# MotorShield.net
KiCad netlist of a schematic drawn in EAGLE
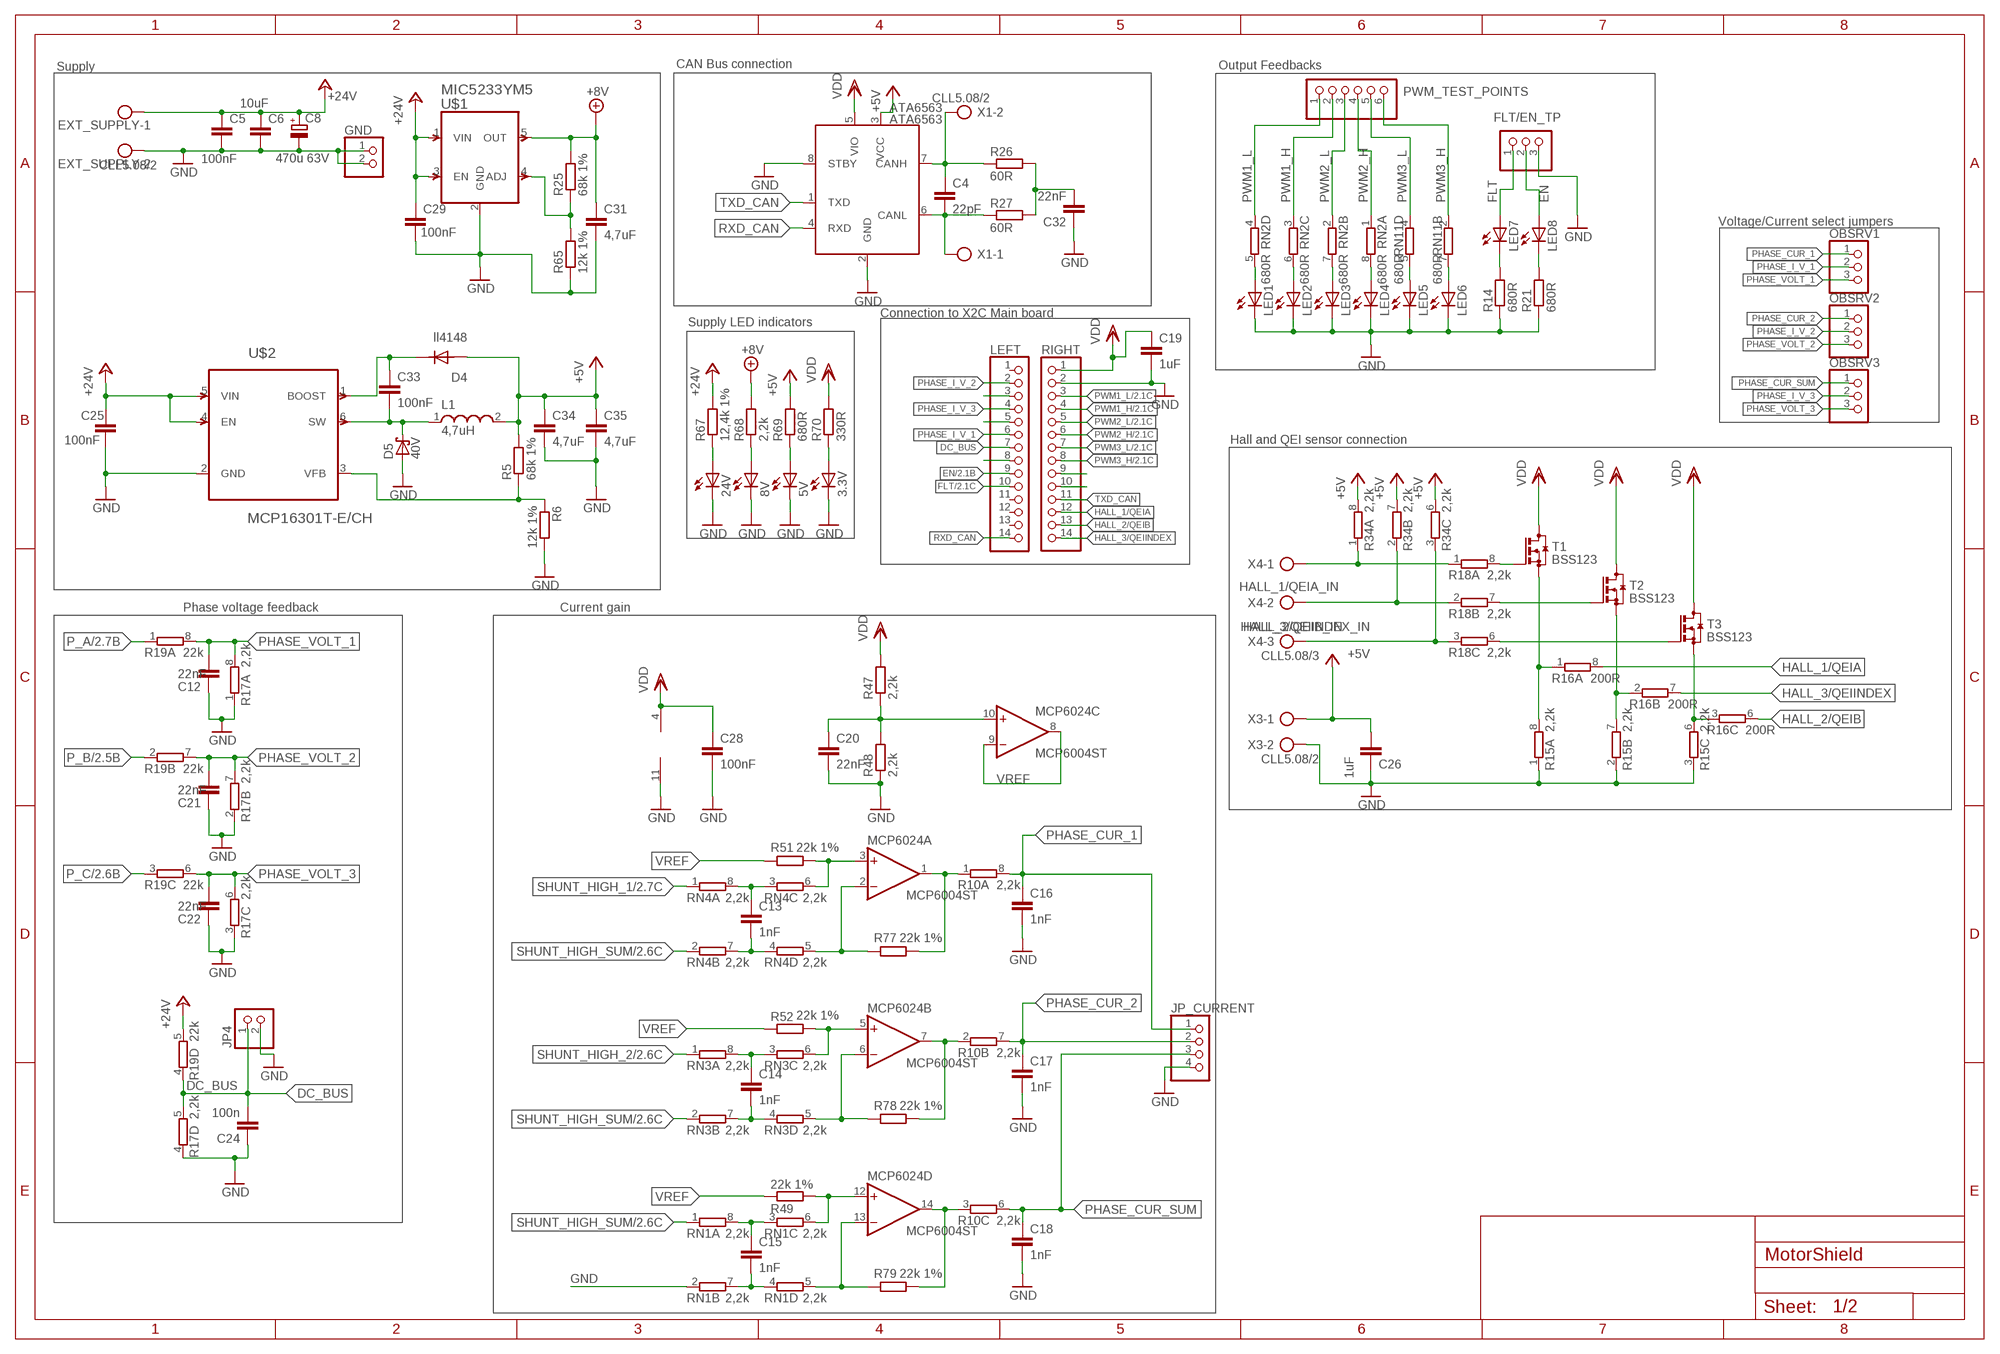
[diagram p0: schematic, sheet 1]
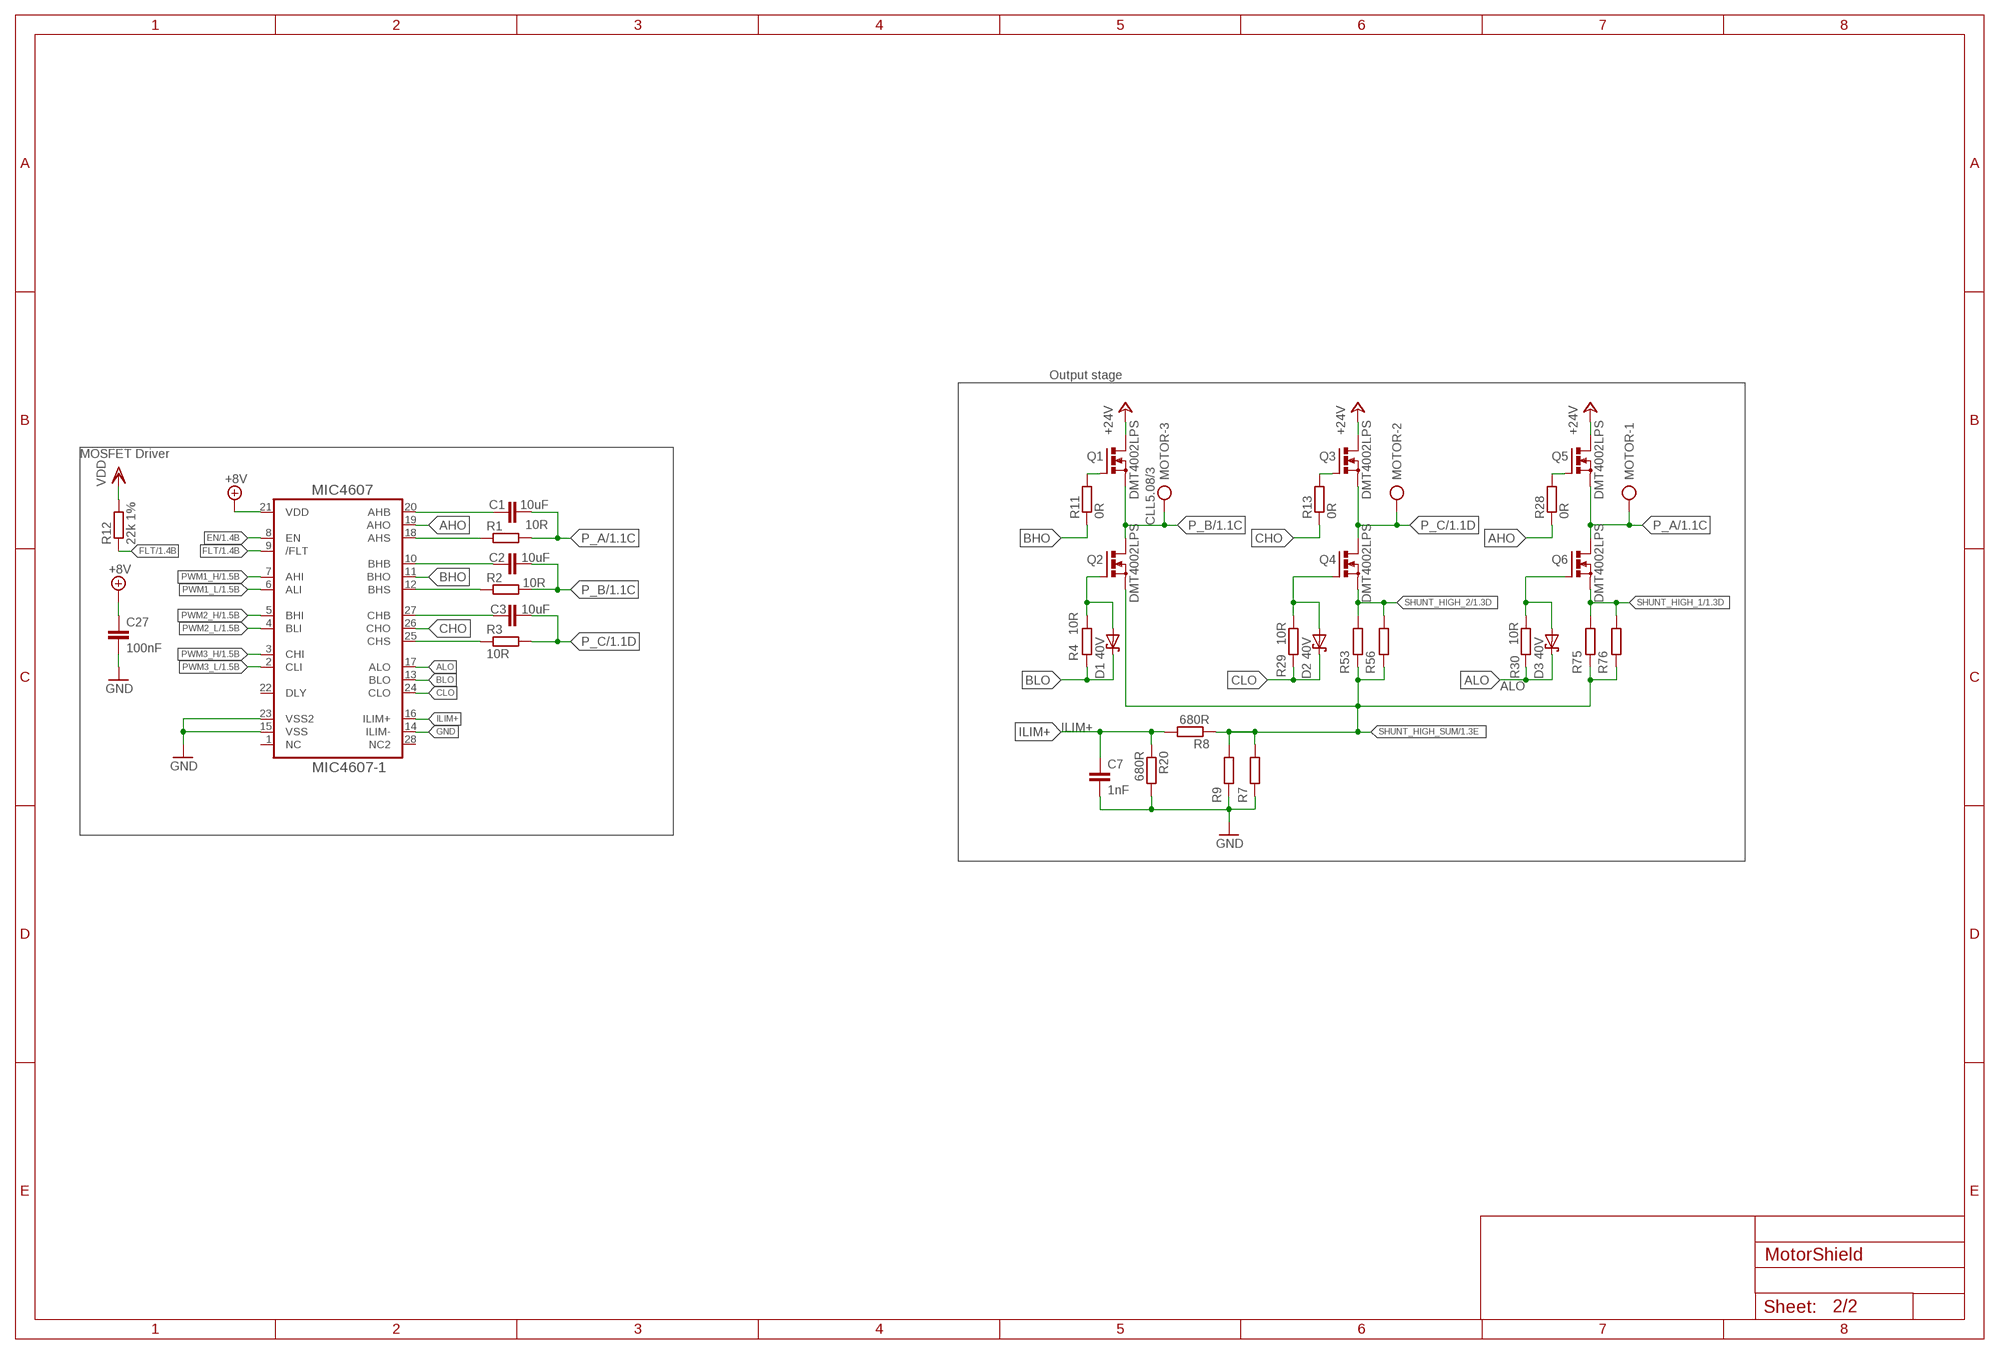
[diagram p1: schematic, sheet 2]

(export (version "E")
  (design (tool "Eeschema 10.0.6"))
  (components
    (comp (ref "3.3V")
      (value "Green")
      (footprint "eagle-import:CHIPLED_0805")
      (libsource (lib "eagle-import") (part "LEDCHIPLED_0805_GREEN"))
    )
    (comp (ref "5V")
      (value "Green")
      (footprint "eagle-import:CHIPLED_0805")
      (libsource (lib "eagle-import") (part "LEDCHIPLED_0805_GREEN"))
    )
    (comp (ref "8V")
      (value "Green")
      (footprint "eagle-import:CHIPLED_0805")
      (libsource (lib "eagle-import") (part "LEDCHIPLED_0805_GREEN"))
    )
    (comp (ref "24V")
      (value "Green")
      (footprint "eagle-import:CHIPLED_0805")
      (libsource (lib "eagle-import") (part "LEDCHIPLED_0805_GREEN"))
    )
    (comp (ref "ATA6563")
      (value "ATA6563")
      (footprint "eagle-import:SOIC-8")
      (libsource (lib "eagle-import") (part "ATA6563"))
    )
    (comp (ref "C4")
      (value "22pF")
      (footprint "eagle-import:C0603K")
      (libsource (lib "eagle-import") (part "C-EU-SMD_0603_22PF_50V"))
    )
    (comp (ref "C5")
      (value "100nF")
      (footprint "eagle-import:C0603K")
      (libsource (lib "eagle-import") (part "C-EU-SMD_0603_100NF_50V"))
    )
    (comp (ref "C6")
      (value "10uF")
      (footprint "eagle-import:C1206")
      (libsource (lib "eagle-import") (part "C-EU-SMD_1206_10UF_50V"))
    )
    (comp (ref "C8")
      (value "470u 63V")
      (footprint "eagle-import:PANASONIC_E")
      (libsource (lib "eagle-import") (part "CPOL-EUE"))
    )
    (comp (ref "C12")
      (value "22nF")
      (footprint "eagle-import:C0603K")
      (libsource (lib "eagle-import") (part "C-EU-SMD_0603_22NF_16V"))
    )
    (comp (ref "C13")
      (value "1nF")
      (footprint "eagle-import:C0603K")
      (libsource (lib "eagle-import") (part "C-EU-SMD_0603_1NF_100V"))
    )
    (comp (ref "C14")
      (value "1nF")
      (footprint "eagle-import:C0603K")
      (libsource (lib "eagle-import") (part "C-EU-SMD_0603_1NF_100V"))
    )
    (comp (ref "C15")
      (value "1nF")
      (footprint "eagle-import:C0603K")
      (libsource (lib "eagle-import") (part "C-EU-SMD_0603_1NF_100V"))
    )
    (comp (ref "C16")
      (value "1nF")
      (footprint "eagle-import:C0603K")
      (libsource (lib "eagle-import") (part "C-EU-SMD_0603_1NF_100V"))
    )
    (comp (ref "C17")
      (value "1nF")
      (footprint "eagle-import:C0603K")
      (libsource (lib "eagle-import") (part "C-EU-SMD_0603_1NF_100V"))
    )
    (comp (ref "C18")
      (value "1nF")
      (footprint "eagle-import:C0603K")
      (libsource (lib "eagle-import") (part "C-EU-SMD_0603_1NF_100V"))
    )
    (comp (ref "C19")
      (value "1uF")
      (footprint "eagle-import:C0603K")
      (libsource (lib "eagle-import") (part "C-EU-SMD_0603_1UF_10V"))
    )
    (comp (ref "C20")
      (value "22nF")
      (footprint "eagle-import:C0603K")
      (libsource (lib "eagle-import") (part "C-EU-SMD_0603_22NF_16V"))
    )
    (comp (ref "C21")
      (value "22nF")
      (footprint "eagle-import:C0603K")
      (libsource (lib "eagle-import") (part "C-EU-SMD_0603_22NF_16V"))
    )
    (comp (ref "C22")
      (value "22nF")
      (footprint "eagle-import:C0603K")
      (libsource (lib "eagle-import") (part "C-EU-SMD_0603_22NF_16V"))
    )
    (comp (ref "C24")
      (value "100n")
      (footprint "eagle-import:C0805")
      (libsource (lib "eagle-import") (part "C-EUC0805"))
    )
    (comp (ref "C25")
      (value "100nF")
      (footprint "eagle-import:C0603K")
      (libsource (lib "eagle-import") (part "C-EU-SMD_0603_100NF_50V"))
    )
    (comp (ref "C26")
      (value "1uF")
      (footprint "eagle-import:C0603K")
      (libsource (lib "eagle-import") (part "C-EU-SMD_0603_1UF_10V"))
    )
    (comp (ref "C28")
      (value "100nF")
      (footprint "eagle-import:C0603K")
      (libsource (lib "eagle-import") (part "C-EU-SMD_0603_100NF_50V"))
    )
    (comp (ref "C29")
      (value "100nF")
      (footprint "eagle-import:C0603K")
      (libsource (lib "eagle-import") (part "C-EU-SMD_0603_100NF_50V"))
    )
    (comp (ref "C31")
      (value "4,7uF")
      (footprint "eagle-import:C0603K")
      (libsource (lib "eagle-import") (part "C-EU-SMD_0603_4,7UF_16V"))
    )
    (comp (ref "C32")
      (value "22nF")
      (footprint "eagle-import:C0603K")
      (libsource (lib "eagle-import") (part "C-EU-SMD_0603_22NF_16V"))
    )
    (comp (ref "C33")
      (value "100nF")
      (footprint "eagle-import:C0603K")
      (libsource (lib "eagle-import") (part "C-EU-SMD_0603_100NF_50V"))
    )
    (comp (ref "C34")
      (value "4,7uF")
      (footprint "eagle-import:C0603K")
      (libsource (lib "eagle-import") (part "C-EU-SMD_0603_4,7UF_16V"))
    )
    (comp (ref "C35")
      (value "4,7uF")
      (footprint "eagle-import:C0603K")
      (libsource (lib "eagle-import") (part "C-EU-SMD_0603_4,7UF_16V"))
    )
    (comp (ref "D4")
      (value "ll4148")
      (footprint "eagle-import:MINIMELF")
      (libsource (lib "eagle-import") (part "1N4148MINIMELF"))
    )
    (comp (ref "D5")
      (value "40V")
      (footprint "eagle-import:MINIMELF")
      (libsource (lib "eagle-import") (part "SCHOTTKY40V"))
    )
    (comp (ref "EXT_SUPPLY")
      (value "CLL5.08/2")
      (footprint "eagle-import:CLL5.08_2")
      (libsource (lib "eagle-import") (part "AK500/2CSAVAROS_CLL5.08/2"))
    )
    (comp (ref "FLT/EN_TP")
      (value "PINHD-1X3")
      (footprint "eagle-import:1X03")
      (libsource (lib "eagle-import") (part "PINHD-1X3"))
    )
    (comp (ref "GND")
      (value "PINHD-1X2")
      (footprint "eagle-import:1X02")
      (libsource (lib "eagle-import") (part "PINHD-1X2"))
    )
    (comp (ref "JP4")
      (value "PINHD-1X2")
      (footprint "eagle-import:1X02")
      (libsource (lib "eagle-import") (part "PINHD-1X2"))
    )
    (comp (ref "JP_CURRENT")
      (value "PINHD-1X4")
      (footprint "eagle-import:1X04")
      (libsource (lib "eagle-import") (part "PINHD-1X4"))
    )
    (comp (ref "L1")
      (value "4,7uH")
      (footprint "eagle-import:WE-TPC_3816")
      (libsource (lib "eagle-import") (part "WE-TPC_3816_4,7UH_0,9A"))
    )
    (comp (ref "LED1")
      (value "Yellow")
      (footprint "eagle-import:CHIPLED_0805")
      (libsource (lib "eagle-import") (part "LEDCHIPLED_0805_YELLOW"))
    )
    (comp (ref "LED2")
      (value "Yellow")
      (footprint "eagle-import:CHIPLED_0805")
      (libsource (lib "eagle-import") (part "LEDCHIPLED_0805_YELLOW"))
    )
    (comp (ref "LED3")
      (value "Yellow")
      (footprint "eagle-import:CHIPLED_0805")
      (libsource (lib "eagle-import") (part "LEDCHIPLED_0805_YELLOW"))
    )
    (comp (ref "LED4")
      (value "Yellow")
      (footprint "eagle-import:CHIPLED_0805")
      (libsource (lib "eagle-import") (part "LEDCHIPLED_0805_YELLOW"))
    )
    (comp (ref "LED5")
      (value "Yellow")
      (footprint "eagle-import:CHIPLED_0805")
      (libsource (lib "eagle-import") (part "LEDCHIPLED_0805_YELLOW"))
    )
    (comp (ref "LED6")
      (value "Yellow")
      (footprint "eagle-import:CHIPLED_0805")
      (libsource (lib "eagle-import") (part "LEDCHIPLED_0805_YELLOW"))
    )
    (comp (ref "LED7")
      (value "Red")
      (footprint "eagle-import:CHIPLED_0805")
      (libsource (lib "eagle-import") (part "LEDCHIPLED_0805_RED"))
    )
    (comp (ref "LED8")
      (value "Red")
      (footprint "eagle-import:CHIPLED_0805")
      (libsource (lib "eagle-import") (part "LEDCHIPLED_0805_RED"))
    )
    (comp (ref "LEFT")
      (value "PINHD-1X14")
      (footprint "eagle-import:1X14")
      (libsource (lib "eagle-import") (part "PINHD-1X14"))
    )
    (comp (ref "MCP6024")
      (value "MCP6004ST")
      (footprint "eagle-import:TSSOP14")
      (libsource (lib "eagle-import") (part "MCP6004ST"))
    )
    (comp (ref "OBSRV1")
      (value "PINHD-1X3")
      (footprint "eagle-import:1X03")
      (libsource (lib "eagle-import") (part "PINHD-1X3"))
    )
    (comp (ref "OBSRV2")
      (value "PINHD-1X3")
      (footprint "eagle-import:1X03")
      (libsource (lib "eagle-import") (part "PINHD-1X3"))
    )
    (comp (ref "OBSRV3")
      (value "PINHD-1X3")
      (footprint "eagle-import:1X03")
      (libsource (lib "eagle-import") (part "PINHD-1X3"))
    )
    (comp (ref "PWM_TEST_POINTS")
      (value "PINHD-1X6")
      (footprint "eagle-import:1X06")
      (libsource (lib "eagle-import") (part "PINHD-1X6"))
    )
    (comp (ref "R5")
      (value "68k 1%")
      (footprint "eagle-import:R0603")
      (libsource (lib "eagle-import") (part "R-EU_SMDR0603_68K_1%"))
    )
    (comp (ref "R6")
      (value "12k 1%")
      (footprint "eagle-import:R0603")
      (libsource (lib "eagle-import") (part "R-EU_SMDR0603_12K_1%"))
    )
    (comp (ref "R10")
      (value "2,2k")
      (footprint "eagle-import:EXBV8V_A")
      (libsource (lib "eagle-import") (part "4R-N2,2K"))
    )
    (comp (ref "R14")
      (value "680R")
      (footprint "eagle-import:R0603")
      (libsource (lib "eagle-import") (part "R-EU_SMDR0603_680R"))
    )
    (comp (ref "R15")
      (value "2,2k")
      (footprint "eagle-import:EXBV8V_A")
      (libsource (lib "eagle-import") (part "4R-N2,2K"))
    )
    (comp (ref "R16")
      (value "200R")
      (footprint "eagle-import:EXBV8V_A")
      (libsource (lib "eagle-import") (part "4R-N200R"))
    )
    (comp (ref "R17")
      (value "2,2k")
      (footprint "eagle-import:EXBV8V_A")
      (libsource (lib "eagle-import") (part "4R-N2,2K"))
    )
    (comp (ref "R18")
      (value "2,2k")
      (footprint "eagle-import:EXBV8V_A")
      (libsource (lib "eagle-import") (part "4R-N2,2K"))
    )
    (comp (ref "R19")
      (value "22k")
      (footprint "eagle-import:EXBV8V_A")
      (libsource (lib "eagle-import") (part "4R-N22K"))
    )
    (comp (ref "R21")
      (value "680R")
      (footprint "eagle-import:R0603")
      (libsource (lib "eagle-import") (part "R-EU_SMDR0603_680R"))
    )
    (comp (ref "R25")
      (value "68k 1%")
      (footprint "eagle-import:R0603")
      (libsource (lib "eagle-import") (part "R-EU_SMDR0603_68K_1%"))
    )
    (comp (ref "R26")
      (value "60R")
      (footprint "eagle-import:R1206")
      (libsource (lib "eagle-import") (part "R-EU_SMDR1206_60R"))
    )
    (comp (ref "R27")
      (value "60R")
      (footprint "eagle-import:R1206")
      (libsource (lib "eagle-import") (part "R-EU_SMDR1206_60R"))
    )
    (comp (ref "R34")
      (value "2,2k")
      (footprint "eagle-import:EXBV8V_A")
      (libsource (lib "eagle-import") (part "4R-N2,2K"))
    )
    (comp (ref "R47")
      (value "2,2k")
      (footprint "eagle-import:R0603")
      (libsource (lib "eagle-import") (part "R-EU_SMDR0603_2,2K"))
    )
    (comp (ref "R48")
      (value "2,2k")
      (footprint "eagle-import:R0603")
      (libsource (lib "eagle-import") (part "R-EU_SMDR0603_2,2K"))
    )
    (comp (ref "R49")
      (value "22k 1%")
      (footprint "eagle-import:R0603")
      (libsource (lib "eagle-import") (part "R-EU_SMDR0603_22K_1%"))
    )
    (comp (ref "R51")
      (value "22k 1%")
      (footprint "eagle-import:R0603")
      (libsource (lib "eagle-import") (part "R-EU_SMDR0603_22K_1%"))
    )
    (comp (ref "R52")
      (value "22k 1%")
      (footprint "eagle-import:R0603")
      (libsource (lib "eagle-import") (part "R-EU_SMDR0603_22K_1%"))
    )
    (comp (ref "R65")
      (value "12k 1%")
      (footprint "eagle-import:R0603")
      (libsource (lib "eagle-import") (part "R-EU_SMDR0603_12K_1%"))
    )
    (comp (ref "R67")
      (value "12,4k 1%")
      (footprint "eagle-import:R0603")
      (libsource (lib "eagle-import") (part "R-EU_SMDR0603_12,4K_1%"))
    )
    (comp (ref "R68")
      (value "2,2k")
      (footprint "eagle-import:R0603")
      (libsource (lib "eagle-import") (part "R-EU_SMDR0603_2,2K"))
    )
    (comp (ref "R69")
      (value "680R")
      (footprint "eagle-import:R0603")
      (libsource (lib "eagle-import") (part "R-EU_SMDR0603_680R"))
    )
    (comp (ref "R70")
      (value "330R")
      (footprint "eagle-import:R0603")
      (libsource (lib "eagle-import") (part "R-EU_SMDR0603_330R"))
    )
    (comp (ref "R77")
      (value "22k 1%")
      (footprint "eagle-import:R0603")
      (libsource (lib "eagle-import") (part "R-EU_SMDR0603_22K_1%"))
    )
    (comp (ref "R78")
      (value "22k 1%")
      (footprint "eagle-import:R0603")
      (libsource (lib "eagle-import") (part "R-EU_SMDR0603_22K_1%"))
    )
    (comp (ref "R79")
      (value "22k 1%")
      (footprint "eagle-import:R0603")
      (libsource (lib "eagle-import") (part "R-EU_SMDR0603_22K_1%"))
    )
    (comp (ref "RIGHT")
      (value "PINHD-1X14")
      (footprint "eagle-import:1X14")
      (libsource (lib "eagle-import") (part "PINHD-1X14"))
    )
    (comp (ref "RN1")
      (value "2,2k")
      (footprint "eagle-import:EXBV8V_A")
      (libsource (lib "eagle-import") (part "4R-N2,2K"))
    )
    (comp (ref "RN2")
      (value "680R")
      (footprint "eagle-import:EXBV8V_A")
      (libsource (lib "eagle-import") (part "4R-N680R"))
    )
    (comp (ref "RN3")
      (value "2,2k")
      (footprint "eagle-import:EXBV8V_A")
      (libsource (lib "eagle-import") (part "4R-N2,2K"))
    )
    (comp (ref "RN4")
      (value "2,2k")
      (footprint "eagle-import:EXBV8V_A")
      (libsource (lib "eagle-import") (part "4R-N2,2K"))
    )
    (comp (ref "RN11")
      (value "680R")
      (footprint "eagle-import:EXBV8V_A")
      (libsource (lib "eagle-import") (part "4R-N680R"))
    )
    (comp (ref "T1")
      (value "BSS123")
      (footprint "eagle-import:SOT23")
      (libsource (lib "eagle-import") (part "BSS123"))
    )
    (comp (ref "T2")
      (value "BSS123")
      (footprint "eagle-import:SOT23")
      (libsource (lib "eagle-import") (part "BSS123"))
    )
    (comp (ref "T3")
      (value "BSS123")
      (footprint "eagle-import:SOT23")
      (libsource (lib "eagle-import") (part "BSS123"))
    )
    (comp (ref "U$1")
      (value "MIC5233YM5")
      (footprint "eagle-import:TSOT23-5")
      (libsource (lib "eagle-import") (part "MIC5233YM5"))
    )
    (comp (ref "U$2")
      (value "MCP16301T-E/CH")
      (footprint "eagle-import:SOT23-6")
      (libsource (lib "eagle-import") (part "MCP16301T-E/CH"))
    )
    (comp (ref "X1")
      (value "CLL5.08/2")
      (footprint "eagle-import:CLL5.08_2")
      (libsource (lib "eagle-import") (part "AK500/2CSAVAROS_CLL5.08/2"))
    )
    (comp (ref "X3")
      (value "CLL5.08/2")
      (footprint "eagle-import:CLL5.08_2")
      (libsource (lib "eagle-import") (part "AK500/2CSAVAROS_CLL5.08/2"))
    )
    (comp (ref "X4")
      (value "CLL5.08/3")
      (footprint "eagle-import:CLL5.08_3")
      (libsource (lib "eagle-import") (part "AK500/3CSAVAROS_CLL5.08/3"))
    )
    (comp (ref "C1")
      (value "10uF")
      (footprint "eagle-import:C0805K")
      (libsource (lib "eagle-import") (part "C-EU-SMD_0805_10UF_16V"))
    )
    (comp (ref "C2")
      (value "10uF")
      (footprint "eagle-import:C0805K")
      (libsource (lib "eagle-import") (part "C-EU-SMD_0805_10UF_16V"))
    )
    (comp (ref "C3")
      (value "10uF")
      (footprint "eagle-import:C0805K")
      (libsource (lib "eagle-import") (part "C-EU-SMD_0805_10UF_16V"))
    )
    (comp (ref "C7")
      (value "1nF")
      (footprint "eagle-import:C0603K")
      (libsource (lib "eagle-import") (part "C-EU-SMD_0603_1NF_100V"))
    )
    (comp (ref "C27")
      (value "100nF")
      (footprint "eagle-import:C0603K")
      (libsource (lib "eagle-import") (part "C-EU-SMD_0603_100NF_50V"))
    )
    (comp (ref "D1")
      (value "40V")
      (footprint "eagle-import:MINIMELF")
      (libsource (lib "eagle-import") (part "SCHOTTKY40V"))
    )
    (comp (ref "D2")
      (value "40V")
      (footprint "eagle-import:MINIMELF")
      (libsource (lib "eagle-import") (part "SCHOTTKY40V"))
    )
    (comp (ref "D3")
      (value "40V")
      (footprint "eagle-import:MINIMELF")
      (libsource (lib "eagle-import") (part "SCHOTTKY40V"))
    )
    (comp (ref "MIC4607")
      (value "MIC4607-1")
      (footprint "eagle-import:TSSOP28")
      (libsource (lib "eagle-import") (part "MIC4607-1"))
    )
    (comp (ref "MOTOR")
      (value "CLL5.08/3")
      (footprint "eagle-import:CLL5.08_3")
      (libsource (lib "eagle-import") (part "AK500/3CSAVAROS_CLL5.08/3"))
    )
    (comp (ref "Q1")
      (value "DMT4002LPS")
      (footprint "eagle-import:PG-TDSON-8_")
      (libsource (lib "eagle-import") (part "BSZ105N04NS_PG-TDSON-8"))
    )
    (comp (ref "Q2")
      (value "DMT4002LPS")
      (footprint "eagle-import:PG-TDSON-8_")
      (libsource (lib "eagle-import") (part "BSZ105N04NS_PG-TDSON-8"))
    )
    (comp (ref "Q3")
      (value "DMT4002LPS")
      (footprint "eagle-import:PG-TDSON-8_")
      (libsource (lib "eagle-import") (part "BSZ105N04NS_PG-TDSON-8"))
    )
    (comp (ref "Q4")
      (value "DMT4002LPS")
      (footprint "eagle-import:PG-TDSON-8_")
      (libsource (lib "eagle-import") (part "BSZ105N04NS_PG-TDSON-8"))
    )
    (comp (ref "Q5")
      (value "DMT4002LPS")
      (footprint "eagle-import:PG-TDSON-8_")
      (libsource (lib "eagle-import") (part "BSZ105N04NS_PG-TDSON-8"))
    )
    (comp (ref "Q6")
      (value "DMT4002LPS")
      (footprint "eagle-import:PG-TDSON-8_")
      (libsource (lib "eagle-import") (part "BSZ105N04NS_PG-TDSON-8"))
    )
    (comp (ref "R1")
      (value "10R")
      (footprint "eagle-import:R0603")
      (libsource (lib "eagle-import") (part "R-EU_SMDR0603_3R"))
    )
    (comp (ref "R2")
      (value "10R")
      (footprint "eagle-import:R0603")
      (libsource (lib "eagle-import") (part "R-EU_SMDR0603_3R"))
    )
    (comp (ref "R3")
      (value "10R")
      (footprint "eagle-import:R0603")
      (libsource (lib "eagle-import") (part "R-EU_SMDR0603_3R"))
    )
    (comp (ref "R4")
      (value "10R")
      (footprint "eagle-import:R0603")
      (libsource (lib "eagle-import") (part "R-EU_SMDR0603_3R"))
    )
    (comp (ref "R7")
      (value "R-EU_SMDR2512")
      (footprint "eagle-import:R2512")
      (libsource (lib "eagle-import") (part "R-EU_SMDR2512"))
    )
    (comp (ref "R8")
      (value "680R")
      (footprint "eagle-import:R0603")
      (libsource (lib "eagle-import") (part "R-EU_SMDR0603_680R"))
    )
    (comp (ref "R9")
      (value "R-EU_SMDR2512")
      (footprint "eagle-import:R2512")
      (libsource (lib "eagle-import") (part "R-EU_SMDR2512"))
    )
    (comp (ref "R11")
      (value "0R")
      (footprint "eagle-import:R0603")
      (libsource (lib "eagle-import") (part "R-EU_SMDR0603_0R"))
    )
    (comp (ref "R12")
      (value "22k 1%")
      (footprint "eagle-import:R0603")
      (libsource (lib "eagle-import") (part "R-EU_SMDR0603_22K_1%"))
    )
    (comp (ref "R13")
      (value "0R")
      (footprint "eagle-import:R0603")
      (libsource (lib "eagle-import") (part "R-EU_SMDR0603_0R"))
    )
    (comp (ref "R20")
      (value "680R")
      (footprint "eagle-import:R0603")
      (libsource (lib "eagle-import") (part "R-EU_SMDR0603_680R"))
    )
    (comp (ref "R28")
      (value "0R")
      (footprint "eagle-import:R0603")
      (libsource (lib "eagle-import") (part "R-EU_SMDR0603_0R"))
    )
    (comp (ref "R29")
      (value "10R")
      (footprint "eagle-import:R0603")
      (libsource (lib "eagle-import") (part "R-EU_SMDR0603_3R"))
    )
    (comp (ref "R30")
      (value "10R")
      (footprint "eagle-import:R0603")
      (libsource (lib "eagle-import") (part "R-EU_SMDR0603_3R"))
    )
    (comp (ref "R53")
      (value "R-EU_SMDR2512")
      (footprint "eagle-import:R2512")
      (libsource (lib "eagle-import") (part "R-EU_SMDR2512"))
    )
    (comp (ref "R56")
      (value "R-EU_SMDR2512")
      (footprint "eagle-import:R2512")
      (libsource (lib "eagle-import") (part "R-EU_SMDR2512"))
    )
    (comp (ref "R75")
      (value "R-EU_SMDR2512")
      (footprint "eagle-import:R2512")
      (libsource (lib "eagle-import") (part "R-EU_SMDR2512"))
    )
    (comp (ref "R76")
      (value "R-EU_SMDR2512")
      (footprint "eagle-import:R2512")
      (libsource (lib "eagle-import") (part "R-EU_SMDR2512"))
    )
  )
  (nets
    (net (code "1") (name "+5V") (class "Default")
      (node (ref "ATA6563") (pin "3") (pinfunction "VCC_3") (pintype "power_in"))
      (node (ref "C26") (pin "1") (pinfunction "1_1") (pintype "passive"))
      (node (ref "C34") (pin "1") (pinfunction "1_1") (pintype "passive"))
      (node (ref "C35") (pin "1") (pinfunction "1_1") (pintype "passive"))
      (node (ref "D4") (pin "A") (pinfunction "A_A") (pintype "passive"))
      (node (ref "L1") (pin "2") (pinfunction "2_2") (pintype "passive"))
      (node (ref "R34") (pin "6") (pinfunction "2_6") (pintype "passive"))
      (node (ref "R34") (pin "7") (pinfunction "2_7") (pintype "passive"))
      (node (ref "R34") (pin "8") (pinfunction "2_8") (pintype "passive"))
      (node (ref "R5") (pin "2") (pinfunction "2_2") (pintype "passive"))
      (node (ref "R69") (pin "2") (pinfunction "2_2") (pintype "passive"))
      (node (ref "X3") (pin "1") (pinfunction "KL_1") (pintype "passive"))
    )
    (net (code "2") (name "+8V") (class "Default")
      (node (ref "C27") (pin "1") (pinfunction "1_1") (pintype "passive"))
      (node (ref "C31") (pin "1") (pinfunction "1_1") (pintype "passive"))
      (node (ref "MIC4607") (pin "21") (pinfunction "VDD_21") (pintype "power_in"))
      (node (ref "R25") (pin "2") (pinfunction "2_2") (pintype "passive"))
      (node (ref "R68") (pin "2") (pinfunction "2_2") (pintype "passive"))
      (node (ref "U$1") (pin "5") (pinfunction "OUT_5") (pintype "output"))
    )
    (net (code "3") (name "+24V") (class "Default")
      (node (ref "C25") (pin "1") (pinfunction "1_1") (pintype "passive"))
      (node (ref "C29") (pin "1") (pinfunction "1_1") (pintype "passive"))
      (node (ref "C5") (pin "1") (pinfunction "1_1") (pintype "passive"))
      (node (ref "C6") (pin "1") (pinfunction "1_1") (pintype "passive"))
      (node (ref "C8") (pin "+") (pinfunction "+_+") (pintype "passive"))
      (node (ref "EXT_SUPPLY") (pin "1") (pinfunction "KL_1") (pintype "passive"))
      (node (ref "Q1") (pin "5") (pinfunction "D_5") (pintype "passive"))
      (node (ref "Q1") (pin "6") (pinfunction "D_6") (pintype "passive"))
      (node (ref "Q1") (pin "7") (pinfunction "D_7") (pintype "passive"))
      (node (ref "Q1") (pin "8") (pinfunction "D_8") (pintype "passive"))
      (node (ref "Q1") (pin "TH") (pinfunction "D_TH") (pintype "passive"))
      (node (ref "Q3") (pin "5") (pinfunction "D_5") (pintype "passive"))
      (node (ref "Q3") (pin "6") (pinfunction "D_6") (pintype "passive"))
      (node (ref "Q3") (pin "7") (pinfunction "D_7") (pintype "passive"))
      (node (ref "Q3") (pin "8") (pinfunction "D_8") (pintype "passive"))
      (node (ref "Q3") (pin "TH") (pinfunction "D_TH") (pintype "passive"))
      (node (ref "Q5") (pin "5") (pinfunction "D_5") (pintype "passive"))
      (node (ref "Q5") (pin "6") (pinfunction "D_6") (pintype "passive"))
      (node (ref "Q5") (pin "7") (pinfunction "D_7") (pintype "passive"))
      (node (ref "Q5") (pin "8") (pinfunction "D_8") (pintype "passive"))
      (node (ref "Q5") (pin "TH") (pinfunction "D_TH") (pintype "passive"))
      (node (ref "R19") (pin "5") (pinfunction "2_5") (pintype "passive"))
      (node (ref "R67") (pin "2") (pinfunction "2_2") (pintype "passive"))
      (node (ref "U$1") (pin "1") (pinfunction "VIN_1") (pintype "input"))
      (node (ref "U$1") (pin "3") (pinfunction "EN_3") (pintype "input"))
      (node (ref "U$2") (pin "4") (pinfunction "EN_4") (pintype "input"))
      (node (ref "U$2") (pin "5") (pinfunction "VIN_5") (pintype "input"))
    )
    (net (code "4") (name "AHO") (class "Default")
      (node (ref "MIC4607") (pin "19") (pinfunction "AHO_19") (pintype "output"))
      (node (ref "R28") (pin "1") (pinfunction "1_1") (pintype "passive"))
    )
    (net (code "5") (name "ALO") (class "Default")
      (node (ref "D3") (pin "C") (pinfunction "C_C") (pintype "passive"))
      (node (ref "MIC4607") (pin "17") (pinfunction "ALO_17") (pintype "output"))
      (node (ref "R30") (pin "2") (pinfunction "2_2") (pintype "passive"))
    )
    (net (code "6") (name "BHO") (class "Default")
      (node (ref "MIC4607") (pin "11") (pinfunction "BHO_11") (pintype "output"))
      (node (ref "R11") (pin "1") (pinfunction "1_1") (pintype "passive"))
    )
    (net (code "7") (name "BLO") (class "Default")
      (node (ref "D1") (pin "C") (pinfunction "C_C") (pintype "passive"))
      (node (ref "MIC4607") (pin "13") (pinfunction "BLO_13") (pintype "output"))
      (node (ref "R4") (pin "1") (pinfunction "1_1") (pintype "passive"))
    )
    (net (code "8") (name "CHO") (class "Default")
      (node (ref "MIC4607") (pin "26") (pinfunction "CHO_26") (pintype "output"))
      (node (ref "R13") (pin "1") (pinfunction "1_1") (pintype "passive"))
    )
    (net (code "9") (name "CLO") (class "Default")
      (node (ref "D2") (pin "C") (pinfunction "C_C") (pintype "passive"))
      (node (ref "MIC4607") (pin "24") (pinfunction "CLO_24") (pintype "output"))
      (node (ref "R29") (pin "2") (pinfunction "2_2") (pintype "passive"))
    )
    (net (code "10") (name "DC_BUS") (class "Default")
      (node (ref "C24") (pin "2") (pinfunction "2_2") (pintype "passive"))
      (node (ref "JP4") (pin "1") (pinfunction "1_1") (pintype "passive"))
      (node (ref "LEFT") (pin "7") (pinfunction "7_7") (pintype "passive"))
      (node (ref "R17") (pin "5") (pinfunction "2_5") (pintype "passive"))
      (node (ref "R19") (pin "4") (pinfunction "1_4") (pintype "passive"))
    )
    (net (code "11") (name "EN") (class "Default")
      (node (ref "FLT/EN_TP") (pin "2") (pinfunction "2_2") (pintype "passive"))
      (node (ref "LED8") (pin "A") (pinfunction "A_A") (pintype "passive"))
      (node (ref "LEFT") (pin "9") (pinfunction "9_9") (pintype "passive"))
      (node (ref "MIC4607") (pin "8") (pinfunction "EN_8") (pintype "input"))
    )
    (net (code "12") (name "FLT") (class "Default")
      (node (ref "FLT/EN_TP") (pin "1") (pinfunction "1_1") (pintype "passive"))
      (node (ref "LED7") (pin "A") (pinfunction "A_A") (pintype "passive"))
      (node (ref "LEFT") (pin "10") (pinfunction "10_10") (pintype "passive"))
      (node (ref "MIC4607") (pin "9") (pinfunction "/FLT_9") (pintype "output"))
      (node (ref "R12") (pin "1") (pinfunction "1_1") (pintype "passive"))
    )
    (net (code "13") (name "GND") (class "Default")
      (node (ref "24V") (pin "C") (pinfunction "C_C") (pintype "passive"))
      (node (ref "3.3V") (pin "C") (pinfunction "C_C") (pintype "passive"))
      (node (ref "5V") (pin "C") (pinfunction "C_C") (pintype "passive"))
      (node (ref "8V") (pin "C") (pinfunction "C_C") (pintype "passive"))
      (node (ref "ATA6563") (pin "2") (pinfunction "GND_2") (pintype "power_in"))
      (node (ref "ATA6563") (pin "8") (pinfunction "STBY_8") (pintype "bidirectional"))
      (node (ref "C12") (pin "2") (pinfunction "2_2") (pintype "passive"))
      (node (ref "C16") (pin "2") (pinfunction "2_2") (pintype "passive"))
      (node (ref "C17") (pin "2") (pinfunction "2_2") (pintype "passive"))
      (node (ref "C18") (pin "2") (pinfunction "2_2") (pintype "passive"))
      (node (ref "C19") (pin "2") (pinfunction "2_2") (pintype "passive"))
      (node (ref "C20") (pin "2") (pinfunction "2_2") (pintype "passive"))
      (node (ref "C21") (pin "2") (pinfunction "2_2") (pintype "passive"))
      (node (ref "C22") (pin "2") (pinfunction "2_2") (pintype "passive"))
      (node (ref "C24") (pin "1") (pinfunction "1_1") (pintype "passive"))
      (node (ref "C25") (pin "2") (pinfunction "2_2") (pintype "passive"))
      (node (ref "C26") (pin "2") (pinfunction "2_2") (pintype "passive"))
      (node (ref "C27") (pin "2") (pinfunction "2_2") (pintype "passive"))
      (node (ref "C28") (pin "2") (pinfunction "2_2") (pintype "passive"))
      (node (ref "C29") (pin "2") (pinfunction "2_2") (pintype "passive"))
      (node (ref "C31") (pin "2") (pinfunction "2_2") (pintype "passive"))
      (node (ref "C32") (pin "1") (pinfunction "1_1") (pintype "passive"))
      (node (ref "C34") (pin "2") (pinfunction "2_2") (pintype "passive"))
      (node (ref "C35") (pin "2") (pinfunction "2_2") (pintype "passive"))
      (node (ref "C5") (pin "2") (pinfunction "2_2") (pintype "passive"))
      (node (ref "C6") (pin "2") (pinfunction "2_2") (pintype "passive"))
      (node (ref "C7") (pin "2") (pinfunction "2_2") (pintype "passive"))
      (node (ref "C8") (pin "-") (pinfunction "-_-") (pintype "passive"))
      (node (ref "D5") (pin "A") (pinfunction "A_A") (pintype "passive"))
      (node (ref "EXT_SUPPLY") (pin "2") (pinfunction "KL_2") (pintype "passive"))
      (node (ref "FLT/EN_TP") (pin "3") (pinfunction "3_3") (pintype "passive"))
      (node (ref "GND") (pin "1") (pinfunction "1_1") (pintype "passive"))
      (node (ref "GND") (pin "2") (pinfunction "2_2") (pintype "passive"))
      (node (ref "JP4") (pin "2") (pinfunction "2_2") (pintype "passive"))
      (node (ref "JP_CURRENT") (pin "4") (pinfunction "4_4") (pintype "passive"))
      (node (ref "LED1") (pin "C") (pinfunction "C_C") (pintype "passive"))
      (node (ref "LED2") (pin "C") (pinfunction "C_C") (pintype "passive"))
      (node (ref "LED3") (pin "C") (pinfunction "C_C") (pintype "passive"))
      (node (ref "LED4") (pin "C") (pinfunction "C_C") (pintype "passive"))
      (node (ref "LED5") (pin "C") (pinfunction "C_C") (pintype "passive"))
      (node (ref "LED6") (pin "C") (pinfunction "C_C") (pintype "passive"))
      (node (ref "MCP6024") (pin "11") (pinfunction "V-_11") (pintype "power_in"))
      (node (ref "MIC4607") (pin "14") (pinfunction "ILIM-_14") (pintype "input"))
      (node (ref "MIC4607") (pin "15") (pinfunction "VSS_15") (pintype "power_in"))
      (node (ref "MIC4607") (pin "23") (pinfunction "VSS2_23") (pintype "power_in"))
      (node (ref "R14") (pin "1") (pinfunction "1_1") (pintype "passive"))
      (node (ref "R15") (pin "1") (pinfunction "1_1") (pintype "passive"))
      (node (ref "R15") (pin "2") (pinfunction "1_2") (pintype "passive"))
      (node (ref "R15") (pin "3") (pinfunction "1_3") (pintype "passive"))
      (node (ref "R17") (pin "1") (pinfunction "1_1") (pintype "passive"))
      (node (ref "R17") (pin "2") (pinfunction "1_2") (pintype "passive"))
      (node (ref "R17") (pin "3") (pinfunction "1_3") (pintype "passive"))
      (node (ref "R17") (pin "4") (pinfunction "1_4") (pintype "passive"))
      (node (ref "R20") (pin "2") (pinfunction "2_2") (pintype "passive"))
      (node (ref "R21") (pin "1") (pinfunction "1_1") (pintype "passive"))
      (node (ref "R48") (pin "1") (pinfunction "1_1") (pintype "passive"))
      (node (ref "R6") (pin "2") (pinfunction "2_2") (pintype "passive"))
      (node (ref "R65") (pin "1") (pinfunction "1_1") (pintype "passive"))
      (node (ref "R7") (pin "1") (pinfunction "1_1") (pintype "passive"))
      (node (ref "R9") (pin "1") (pinfunction "1_1") (pintype "passive"))
      (node (ref "RIGHT") (pin "2") (pinfunction "2_2") (pintype "passive"))
      (node (ref "RN1") (pin "2") (pinfunction "1_2") (pintype "passive"))
      (node (ref "U$1") (pin "2") (pinfunction "GND_2") (pintype "passive"))
      (node (ref "U$2") (pin "2") (pinfunction "GND_2") (pintype "passive"))
      (node (ref "X3") (pin "2") (pinfunction "KL_2") (pintype "passive"))
    )
    (net (code "14") (name "HALL_1{slash}QEIA") (class "Default")
      (node (ref "R16") (pin "8") (pinfunction "2_8") (pintype "passive"))
      (node (ref "RIGHT") (pin "12") (pinfunction "12_12") (pintype "passive"))
    )
    (net (code "15") (name "HALL_1{slash}QEIA_IN") (class "Default")
      (node (ref "R18") (pin "1") (pinfunction "1_1") (pintype "passive"))
      (node (ref "R34") (pin "1") (pinfunction "1_1") (pintype "passive"))
      (node (ref "X4") (pin "1") (pinfunction "KL_1") (pintype "passive"))
    )
    (net (code "16") (name "HALL_2{slash}QEIB") (class "Default")
      (node (ref "R16") (pin "6") (pinfunction "2_6") (pintype "passive"))
      (node (ref "RIGHT") (pin "13") (pinfunction "13_13") (pintype "passive"))
    )
    (net (code "17") (name "HALL_2{slash}QEIB_IN") (class "Default")
      (node (ref "R18") (pin "3") (pinfunction "1_3") (pintype "passive"))
      (node (ref "R34") (pin "3") (pinfunction "1_3") (pintype "passive"))
      (node (ref "X4") (pin "3") (pinfunction "KL_3") (pintype "passive"))
    )
    (net (code "18") (name "HALL_3{slash}QEIINDEX") (class "Default")
      (node (ref "R16") (pin "7") (pinfunction "2_7") (pintype "passive"))
      (node (ref "RIGHT") (pin "14") (pinfunction "14_14") (pintype "passive"))
    )
    (net (code "19") (name "HALL_3{slash}QEIINDEX_IN") (class "Default")
      (node (ref "R18") (pin "2") (pinfunction "1_2") (pintype "passive"))
      (node (ref "R34") (pin "2") (pinfunction "1_2") (pintype "passive"))
      (node (ref "X4") (pin "2") (pinfunction "KL_2") (pintype "passive"))
    )
    (net (code "20") (name "ILIM+") (class "Default")
      (node (ref "C7") (pin "1") (pinfunction "1_1") (pintype "passive"))
      (node (ref "MIC4607") (pin "16") (pinfunction "ILIM+_16") (pintype "input"))
      (node (ref "R20") (pin "1") (pinfunction "1_1") (pintype "passive"))
      (node (ref "R8") (pin "2") (pinfunction "2_2") (pintype "passive"))
    )
    (net (code "21") (name "Net-(3.3V-PadA)") (class "Default")
      (node (ref "3.3V") (pin "A") (pinfunction "A_A") (pintype "passive"))
      (node (ref "R70") (pin "1") (pinfunction "1_1") (pintype "passive"))
    )
    (net (code "22") (name "Net-(5V-PadA)") (class "Default")
      (node (ref "5V") (pin "A") (pinfunction "A_A") (pintype "passive"))
      (node (ref "R69") (pin "1") (pinfunction "1_1") (pintype "passive"))
    )
    (net (code "23") (name "Net-(8V-PadA)") (class "Default")
      (node (ref "8V") (pin "A") (pinfunction "A_A") (pintype "passive"))
      (node (ref "R68") (pin "1") (pinfunction "1_1") (pintype "passive"))
    )
    (net (code "24") (name "Net-(24V-PadA)") (class "Default")
      (node (ref "24V") (pin "A") (pinfunction "A_A") (pintype "passive"))
      (node (ref "R67") (pin "1") (pinfunction "1_1") (pintype "passive"))
    )
    (net (code "25") (name "Net-(ATA6563-CANH)") (class "Default")
      (node (ref "ATA6563") (pin "7") (pinfunction "CANH_7") (pintype "output"))
      (node (ref "C4") (pin "1") (pinfunction "1_1") (pintype "passive"))
      (node (ref "R26") (pin "1") (pinfunction "1_1") (pintype "passive"))
      (node (ref "X1") (pin "2") (pinfunction "KL_2") (pintype "passive"))
    )
    (net (code "26") (name "Net-(ATA6563-CANL)") (class "Default")
      (node (ref "ATA6563") (pin "6") (pinfunction "CANL_6") (pintype "output"))
      (node (ref "C4") (pin "2") (pinfunction "2_2") (pintype "passive"))
      (node (ref "R27") (pin "1") (pinfunction "1_1") (pintype "passive"))
      (node (ref "X1") (pin "1") (pinfunction "KL_1") (pintype "passive"))
    )
    (net (code "27") (name "Net-(C32-Pad2)") (class "Default")
      (node (ref "C32") (pin "2") (pinfunction "2_2") (pintype "passive"))
      (node (ref "R26") (pin "2") (pinfunction "2_2") (pintype "passive"))
      (node (ref "R27") (pin "2") (pinfunction "2_2") (pintype "passive"))
    )
    (net (code "28") (name "Net-(LED7-PadC)") (class "Default")
      (node (ref "LED7") (pin "C") (pinfunction "C_C") (pintype "passive"))
      (node (ref "R14") (pin "2") (pinfunction "2_2") (pintype "passive"))
    )
    (net (code "29") (name "Net-(LED8-PadC)") (class "Default")
      (node (ref "LED8") (pin "C") (pinfunction "C_C") (pintype "passive"))
      (node (ref "R21") (pin "2") (pinfunction "2_2") (pintype "passive"))
    )
    (net (code "30") (name "Net-(MCP6024A-+IN)") (class "Default")
      (node (ref "MCP6024") (pin "3") (pinfunction "+IN_3") (pintype "input"))
      (node (ref "R51") (pin "2") (pinfunction "2_2") (pintype "passive"))
      (node (ref "RN4") (pin "6") (pinfunction "2_6") (pintype "passive"))
    )
    (net (code "31") (name "Net-(MCP6024A--IN)") (class "Default")
      (node (ref "MCP6024") (pin "2") (pinfunction "-IN_2") (pintype "input"))
      (node (ref "R77") (pin "1") (pinfunction "1_1") (pintype "passive"))
      (node (ref "RN4") (pin "5") (pinfunction "2_5") (pintype "passive"))
    )
    (net (code "32") (name "Net-(MCP6024A-OUT)") (class "Default")
      (node (ref "MCP6024") (pin "1") (pinfunction "OUT_1") (pintype "output"))
      (node (ref "R10") (pin "1") (pinfunction "1_1") (pintype "passive"))
      (node (ref "R77") (pin "2") (pinfunction "2_2") (pintype "passive"))
    )
    (net (code "33") (name "Net-(MCP6024B-+IN)") (class "Default")
      (node (ref "MCP6024") (pin "5") (pinfunction "+IN_5") (pintype "input"))
      (node (ref "R52") (pin "2") (pinfunction "2_2") (pintype "passive"))
      (node (ref "RN3") (pin "6") (pinfunction "2_6") (pintype "passive"))
    )
    (net (code "34") (name "Net-(MCP6024B--IN)") (class "Default")
      (node (ref "MCP6024") (pin "6") (pinfunction "-IN_6") (pintype "input"))
      (node (ref "R78") (pin "1") (pinfunction "1_1") (pintype "passive"))
      (node (ref "RN3") (pin "5") (pinfunction "2_5") (pintype "passive"))
    )
    (net (code "35") (name "Net-(MCP6024B-OUT)") (class "Default")
      (node (ref "MCP6024") (pin "7") (pinfunction "OUT_7") (pintype "output"))
      (node (ref "R10") (pin "2") (pinfunction "1_2") (pintype "passive"))
      (node (ref "R78") (pin "2") (pinfunction "2_2") (pintype "passive"))
    )
    (net (code "36") (name "Net-(MCP6024C-+IN)") (class "Default")
      (node (ref "C20") (pin "1") (pinfunction "1_1") (pintype "passive"))
      (node (ref "MCP6024") (pin "10") (pinfunction "+IN_10") (pintype "input"))
      (node (ref "R47") (pin "1") (pinfunction "1_1") (pintype "passive"))
      (node (ref "R48") (pin "2") (pinfunction "2_2") (pintype "passive"))
    )
    (net (code "37") (name "Net-(MCP6024D-+IN)") (class "Default")
      (node (ref "MCP6024") (pin "12") (pinfunction "+IN_12") (pintype "input"))
      (node (ref "R49") (pin "2") (pinfunction "2_2") (pintype "passive"))
      (node (ref "RN1") (pin "6") (pinfunction "2_6") (pintype "passive"))
    )
    (net (code "38") (name "Net-(MCP6024D--IN)") (class "Default")
      (node (ref "MCP6024") (pin "13") (pinfunction "-IN_13") (pintype "input"))
      (node (ref "R79") (pin "1") (pinfunction "1_1") (pintype "passive"))
      (node (ref "RN1") (pin "5") (pinfunction "2_5") (pintype "passive"))
    )
    (net (code "39") (name "Net-(MCP6024D-OUT)") (class "Default")
      (node (ref "MCP6024") (pin "14") (pinfunction "OUT_14") (pintype "output"))
      (node (ref "R10") (pin "3") (pinfunction "1_3") (pintype "passive"))
      (node (ref "R79") (pin "2") (pinfunction "2_2") (pintype "passive"))
    )
    (net (code "40") (name "Net-(MIC4607-AHB)") (class "Default")
      (node (ref "C1") (pin "1") (pinfunction "1_1") (pintype "passive"))
      (node (ref "MIC4607") (pin "20") (pinfunction "AHB_20") (pintype "output"))
    )
    (net (code "41") (name "Net-(MIC4607-AHS)") (class "Default")
      (node (ref "MIC4607") (pin "18") (pinfunction "AHS_18") (pintype "output"))
      (node (ref "R1") (pin "1") (pinfunction "1_1") (pintype "passive"))
    )
    (net (code "42") (name "Net-(MIC4607-BHB)") (class "Default")
      (node (ref "C2") (pin "1") (pinfunction "1_1") (pintype "passive"))
      (node (ref "MIC4607") (pin "10") (pinfunction "BHB_10") (pintype "output"))
    )
    (net (code "43") (name "Net-(MIC4607-BHS)") (class "Default")
      (node (ref "MIC4607") (pin "12") (pinfunction "BHS_12") (pintype "output"))
      (node (ref "R2") (pin "1") (pinfunction "1_1") (pintype "passive"))
    )
    (net (code "44") (name "Net-(MIC4607-CHB)") (class "Default")
      (node (ref "C3") (pin "1") (pinfunction "1_1") (pintype "passive"))
      (node (ref "MIC4607") (pin "27") (pinfunction "CHB_27") (pintype "output"))
    )
    (net (code "45") (name "Net-(MIC4607-CHS)") (class "Default")
      (node (ref "MIC4607") (pin "25") (pinfunction "CHS_25") (pintype "output"))
      (node (ref "R3") (pin "1") (pinfunction "1_1") (pintype "passive"))
    )
    (net (code "46") (name "Net-(Q1-G)") (class "Default")
      (node (ref "Q1") (pin "4") (pinfunction "G_4") (pintype "passive"))
      (node (ref "R11") (pin "2") (pinfunction "2_2") (pintype "passive"))
    )
    (net (code "47") (name "Net-(Q2-G)") (class "Default")
      (node (ref "D1") (pin "A") (pinfunction "A_A") (pintype "passive"))
      (node (ref "Q2") (pin "4") (pinfunction "G_4") (pintype "passive"))
      (node (ref "R4") (pin "2") (pinfunction "2_2") (pintype "passive"))
    )
    (net (code "48") (name "Net-(Q3-G)") (class "Default")
      (node (ref "Q3") (pin "4") (pinfunction "G_4") (pintype "passive"))
      (node (ref "R13") (pin "2") (pinfunction "2_2") (pintype "passive"))
    )
    (net (code "49") (name "Net-(Q4-G)") (class "Default")
      (node (ref "D2") (pin "A") (pinfunction "A_A") (pintype "passive"))
      (node (ref "Q4") (pin "4") (pinfunction "G_4") (pintype "passive"))
      (node (ref "R29") (pin "1") (pinfunction "1_1") (pintype "passive"))
    )
    (net (code "50") (name "Net-(Q5-G)") (class "Default")
      (node (ref "Q5") (pin "4") (pinfunction "G_4") (pintype "passive"))
      (node (ref "R28") (pin "2") (pinfunction "2_2") (pintype "passive"))
    )
    (net (code "51") (name "Net-(Q6-G)") (class "Default")
      (node (ref "D3") (pin "A") (pinfunction "A_A") (pintype "passive"))
      (node (ref "Q6") (pin "4") (pinfunction "G_4") (pintype "passive"))
      (node (ref "R30") (pin "1") (pinfunction "1_1") (pintype "passive"))
    )
    (net (code "52") (name "Net-(R15A-2)") (class "Default")
      (node (ref "R15") (pin "8") (pinfunction "2_8") (pintype "passive"))
      (node (ref "R16") (pin "1") (pinfunction "1_1") (pintype "passive"))
      (node (ref "T1") (pin "2") (pinfunction "S_2") (pintype "passive"))
    )
    (net (code "53") (name "Net-(R15B-2)") (class "Default")
      (node (ref "R15") (pin "7") (pinfunction "2_7") (pintype "passive"))
      (node (ref "R16") (pin "2") (pinfunction "1_2") (pintype "passive"))
      (node (ref "T2") (pin "2") (pinfunction "S_2") (pintype "passive"))
    )
    (net (code "54") (name "Net-(R15C-2)") (class "Default")
      (node (ref "R15") (pin "6") (pinfunction "2_6") (pintype "passive"))
      (node (ref "R16") (pin "3") (pinfunction "1_3") (pintype "passive"))
      (node (ref "T3") (pin "2") (pinfunction "S_2") (pintype "passive"))
    )
    (net (code "55") (name "Net-(R18A-2)") (class "Default")
      (node (ref "R18") (pin "8") (pinfunction "2_8") (pintype "passive"))
      (node (ref "T1") (pin "1") (pinfunction "G_1") (pintype "passive"))
    )
    (net (code "56") (name "Net-(R18B-2)") (class "Default")
      (node (ref "R18") (pin "7") (pinfunction "2_7") (pintype "passive"))
      (node (ref "T2") (pin "1") (pinfunction "G_1") (pintype "passive"))
    )
    (net (code "57") (name "Net-(R18C-2)") (class "Default")
      (node (ref "R18") (pin "6") (pinfunction "2_6") (pintype "passive"))
      (node (ref "T3") (pin "1") (pinfunction "G_1") (pintype "passive"))
    )
    (net (code "58") (name "Net-(RN1A-2)") (class "Default")
      (node (ref "C15") (pin "1") (pinfunction "1_1") (pintype "passive"))
      (node (ref "RN1") (pin "3") (pinfunction "1_3") (pintype "passive"))
      (node (ref "RN1") (pin "8") (pinfunction "2_8") (pintype "passive"))
    )
    (net (code "59") (name "Net-(RN1B-2)") (class "Default")
      (node (ref "C15") (pin "2") (pinfunction "2_2") (pintype "passive"))
      (node (ref "RN1") (pin "4") (pinfunction "1_4") (pintype "passive"))
      (node (ref "RN1") (pin "7") (pinfunction "2_7") (pintype "passive"))
    )
    (net (code "60") (name "Net-(RN2A-2)") (class "Default")
      (node (ref "LED4") (pin "A") (pinfunction "A_A") (pintype "passive"))
      (node (ref "RN2") (pin "8") (pinfunction "2_8") (pintype "passive"))
    )
    (net (code "61") (name "Net-(RN2B-2)") (class "Default")
      (node (ref "LED3") (pin "A") (pinfunction "A_A") (pintype "passive"))
      (node (ref "RN2") (pin "7") (pinfunction "2_7") (pintype "passive"))
    )
    (net (code "62") (name "Net-(RN2C-2)") (class "Default")
      (node (ref "LED2") (pin "A") (pinfunction "A_A") (pintype "passive"))
      (node (ref "RN2") (pin "6") (pinfunction "2_6") (pintype "passive"))
    )
    (net (code "63") (name "Net-(RN2D-2)") (class "Default")
      (node (ref "LED1") (pin "A") (pinfunction "A_A") (pintype "passive"))
      (node (ref "RN2") (pin "5") (pinfunction "2_5") (pintype "passive"))
    )
    (net (code "64") (name "Net-(RN3A-2)") (class "Default")
      (node (ref "C14") (pin "1") (pinfunction "1_1") (pintype "passive"))
      (node (ref "RN3") (pin "3") (pinfunction "1_3") (pintype "passive"))
      (node (ref "RN3") (pin "8") (pinfunction "2_8") (pintype "passive"))
    )
    (net (code "65") (name "Net-(RN3B-2)") (class "Default")
      (node (ref "C14") (pin "2") (pinfunction "2_2") (pintype "passive"))
      (node (ref "RN3") (pin "4") (pinfunction "1_4") (pintype "passive"))
      (node (ref "RN3") (pin "7") (pinfunction "2_7") (pintype "passive"))
    )
    (net (code "66") (name "Net-(RN4A-2)") (class "Default")
      (node (ref "C13") (pin "1") (pinfunction "1_1") (pintype "passive"))
      (node (ref "RN4") (pin "3") (pinfunction "1_3") (pintype "passive"))
      (node (ref "RN4") (pin "8") (pinfunction "2_8") (pintype "passive"))
    )
    (net (code "67") (name "Net-(RN4B-2)") (class "Default")
      (node (ref "C13") (pin "2") (pinfunction "2_2") (pintype "passive"))
      (node (ref "RN4") (pin "4") (pinfunction "1_4") (pintype "passive"))
      (node (ref "RN4") (pin "7") (pinfunction "2_7") (pintype "passive"))
    )
    (net (code "68") (name "Net-(RN11B-2)") (class "Default")
      (node (ref "LED6") (pin "A") (pinfunction "A_A") (pintype "passive"))
      (node (ref "RN11") (pin "7") (pinfunction "2_7") (pintype "passive"))
    )
    (net (code "69") (name "Net-(RN11D-2)") (class "Default")
      (node (ref "LED5") (pin "A") (pinfunction "A_A") (pintype "passive"))
      (node (ref "RN11") (pin "5") (pinfunction "2_5") (pintype "passive"))
    )
    (net (code "70") (name "Net-(U$1-ADJ)") (class "Default")
      (node (ref "R25") (pin "1") (pinfunction "1_1") (pintype "passive"))
      (node (ref "R65") (pin "2") (pinfunction "2_2") (pintype "passive"))
      (node (ref "U$1") (pin "4") (pinfunction "ADJ_4") (pintype "output"))
    )
    (net (code "71") (name "Net-(U$2-BOOST)") (class "Default")
      (node (ref "C33") (pin "1") (pinfunction "1_1") (pintype "passive"))
      (node (ref "D4") (pin "C") (pinfunction "C_C") (pintype "passive"))
      (node (ref "U$2") (pin "1") (pinfunction "BOOST_1") (pintype "output"))
    )
    (net (code "72") (name "Net-(U$2-SW)") (class "Default")
      (node (ref "C33") (pin "2") (pinfunction "2_2") (pintype "passive"))
      (node (ref "D5") (pin "C") (pinfunction "C_C") (pintype "passive"))
      (node (ref "L1") (pin "1") (pinfunction "1_1") (pintype "passive"))
      (node (ref "U$2") (pin "6") (pinfunction "SW_6") (pintype "output"))
    )
    (net (code "73") (name "Net-(U$2-VFB)") (class "Default")
      (node (ref "R5") (pin "1") (pinfunction "1_1") (pintype "passive"))
      (node (ref "R6") (pin "1") (pinfunction "1_1") (pintype "passive"))
      (node (ref "U$2") (pin "3") (pinfunction "VFB_3") (pintype "input"))
    )
    (net (code "74") (name "PHASE_CUR_1") (class "Default")
      (node (ref "C16") (pin "1") (pinfunction "1_1") (pintype "passive"))
      (node (ref "JP_CURRENT") (pin "1") (pinfunction "1_1") (pintype "passive"))
      (node (ref "OBSRV1") (pin "1") (pinfunction "1_1") (pintype "passive"))
      (node (ref "R10") (pin "8") (pinfunction "2_8") (pintype "passive"))
    )
    (net (code "75") (name "PHASE_CUR_2") (class "Default")
      (node (ref "C17") (pin "1") (pinfunction "1_1") (pintype "passive"))
      (node (ref "JP_CURRENT") (pin "2") (pinfunction "2_2") (pintype "passive"))
      (node (ref "OBSRV2") (pin "1") (pinfunction "1_1") (pintype "passive"))
      (node (ref "R10") (pin "7") (pinfunction "2_7") (pintype "passive"))
    )
    (net (code "76") (name "PHASE_CUR_SUM") (class "Default")
      (node (ref "C18") (pin "1") (pinfunction "1_1") (pintype "passive"))
      (node (ref "JP_CURRENT") (pin "3") (pinfunction "3_3") (pintype "passive"))
      (node (ref "OBSRV3") (pin "1") (pinfunction "1_1") (pintype "passive"))
      (node (ref "R10") (pin "6") (pinfunction "2_6") (pintype "passive"))
    )
    (net (code "77") (name "PHASE_I_V_1") (class "Default")
      (node (ref "LEFT") (pin "6") (pinfunction "6_6") (pintype "passive"))
      (node (ref "OBSRV1") (pin "2") (pinfunction "2_2") (pintype "passive"))
    )
    (net (code "78") (name "PHASE_I_V_2") (class "Default")
      (node (ref "LEFT") (pin "2") (pinfunction "2_2") (pintype "passive"))
      (node (ref "OBSRV2") (pin "2") (pinfunction "2_2") (pintype "passive"))
    )
    (net (code "79") (name "PHASE_I_V_3") (class "Default")
      (node (ref "LEFT") (pin "4") (pinfunction "4_4") (pintype "passive"))
      (node (ref "OBSRV3") (pin "2") (pinfunction "2_2") (pintype "passive"))
    )
    (net (code "80") (name "PHASE_VOLT_1") (class "Default")
      (node (ref "C12") (pin "1") (pinfunction "1_1") (pintype "passive"))
      (node (ref "OBSRV1") (pin "3") (pinfunction "3_3") (pintype "passive"))
      (node (ref "R17") (pin "8") (pinfunction "2_8") (pintype "passive"))
      (node (ref "R19") (pin "8") (pinfunction "2_8") (pintype "passive"))
    )
    (net (code "81") (name "PHASE_VOLT_2") (class "Default")
      (node (ref "C21") (pin "1") (pinfunction "1_1") (pintype "passive"))
      (node (ref "OBSRV2") (pin "3") (pinfunction "3_3") (pintype "passive"))
      (node (ref "R17") (pin "7") (pinfunction "2_7") (pintype "passive"))
      (node (ref "R19") (pin "7") (pinfunction "2_7") (pintype "passive"))
    )
    (net (code "82") (name "PHASE_VOLT_3") (class "Default")
      (node (ref "C22") (pin "1") (pinfunction "1_1") (pintype "passive"))
      (node (ref "OBSRV3") (pin "3") (pinfunction "3_3") (pintype "passive"))
      (node (ref "R17") (pin "6") (pinfunction "2_6") (pintype "passive"))
      (node (ref "R19") (pin "6") (pinfunction "2_6") (pintype "passive"))
    )
    (net (code "83") (name "PWM1_H") (class "Default")
      (node (ref "MIC4607") (pin "7") (pinfunction "AHI_7") (pintype "input"))
      (node (ref "PWM_TEST_POINTS") (pin "2") (pinfunction "2_2") (pintype "passive"))
      (node (ref "RIGHT") (pin "4") (pinfunction "4_4") (pintype "passive"))
      (node (ref "RN2") (pin "3") (pinfunction "1_3") (pintype "passive"))
    )
    (net (code "84") (name "PWM1_L") (class "Default")
      (node (ref "MIC4607") (pin "6") (pinfunction "ALI_6") (pintype "input"))
      (node (ref "PWM_TEST_POINTS") (pin "1") (pinfunction "1_1") (pintype "passive"))
      (node (ref "RIGHT") (pin "3") (pinfunction "3_3") (pintype "passive"))
      (node (ref "RN2") (pin "4") (pinfunction "1_4") (pintype "passive"))
    )
    (net (code "85") (name "PWM2_H") (class "Default")
      (node (ref "MIC4607") (pin "5") (pinfunction "BHI_5") (pintype "input"))
      (node (ref "PWM_TEST_POINTS") (pin "4") (pinfunction "4_4") (pintype "passive"))
      (node (ref "RIGHT") (pin "6") (pinfunction "6_6") (pintype "passive"))
      (node (ref "RN2") (pin "1") (pinfunction "1_1") (pintype "passive"))
    )
    (net (code "86") (name "PWM2_L") (class "Default")
      (node (ref "MIC4607") (pin "4") (pinfunction "BLI_4") (pintype "input"))
      (node (ref "PWM_TEST_POINTS") (pin "3") (pinfunction "3_3") (pintype "passive"))
      (node (ref "RIGHT") (pin "5") (pinfunction "5_5") (pintype "passive"))
      (node (ref "RN2") (pin "2") (pinfunction "1_2") (pintype "passive"))
    )
    (net (code "87") (name "PWM3_H") (class "Default")
      (node (ref "MIC4607") (pin "3") (pinfunction "CHI_3") (pintype "input"))
      (node (ref "PWM_TEST_POINTS") (pin "6") (pinfunction "6_6") (pintype "passive"))
      (node (ref "RIGHT") (pin "8") (pinfunction "8_8") (pintype "passive"))
      (node (ref "RN11") (pin "2") (pinfunction "1_2") (pintype "passive"))
    )
    (net (code "88") (name "PWM3_L") (class "Default")
      (node (ref "MIC4607") (pin "2") (pinfunction "CLI_2") (pintype "input"))
      (node (ref "PWM_TEST_POINTS") (pin "5") (pinfunction "5_5") (pintype "passive"))
      (node (ref "RIGHT") (pin "7") (pinfunction "7_7") (pintype "passive"))
      (node (ref "RN11") (pin "4") (pinfunction "1_4") (pintype "passive"))
    )
    (net (code "89") (name "P_A") (class "Default")
      (node (ref "C1") (pin "2") (pinfunction "2_2") (pintype "passive"))
      (node (ref "MOTOR") (pin "1") (pinfunction "KL_1") (pintype "passive"))
      (node (ref "Q5") (pin "1") (pinfunction "S_1") (pintype "passive"))
      (node (ref "Q5") (pin "2") (pinfunction "S_2") (pintype "passive"))
      (node (ref "Q5") (pin "3") (pinfunction "S_3") (pintype "passive"))
      (node (ref "Q6") (pin "5") (pinfunction "D_5") (pintype "passive"))
      (node (ref "Q6") (pin "6") (pinfunction "D_6") (pintype "passive"))
      (node (ref "Q6") (pin "7") (pinfunction "D_7") (pintype "passive"))
      (node (ref "Q6") (pin "8") (pinfunction "D_8") (pintype "passive"))
      (node (ref "Q6") (pin "TH") (pinfunction "D_TH") (pintype "passive"))
      (node (ref "R1") (pin "2") (pinfunction "2_2") (pintype "passive"))
      (node (ref "R19") (pin "1") (pinfunction "1_1") (pintype "passive"))
    )
    (net (code "90") (name "P_B") (class "Default")
      (node (ref "C2") (pin "2") (pinfunction "2_2") (pintype "passive"))
      (node (ref "MOTOR") (pin "3") (pinfunction "KL_3") (pintype "passive"))
      (node (ref "Q1") (pin "1") (pinfunction "S_1") (pintype "passive"))
      (node (ref "Q1") (pin "2") (pinfunction "S_2") (pintype "passive"))
      (node (ref "Q1") (pin "3") (pinfunction "S_3") (pintype "passive"))
      (node (ref "Q2") (pin "5") (pinfunction "D_5") (pintype "passive"))
      (node (ref "Q2") (pin "6") (pinfunction "D_6") (pintype "passive"))
      (node (ref "Q2") (pin "7") (pinfunction "D_7") (pintype "passive"))
      (node (ref "Q2") (pin "8") (pinfunction "D_8") (pintype "passive"))
      (node (ref "Q2") (pin "TH") (pinfunction "D_TH") (pintype "passive"))
      (node (ref "R19") (pin "2") (pinfunction "1_2") (pintype "passive"))
      (node (ref "R2") (pin "2") (pinfunction "2_2") (pintype "passive"))
    )
    (net (code "91") (name "P_C") (class "Default")
      (node (ref "C3") (pin "2") (pinfunction "2_2") (pintype "passive"))
      (node (ref "MOTOR") (pin "2") (pinfunction "KL_2") (pintype "passive"))
      (node (ref "Q3") (pin "1") (pinfunction "S_1") (pintype "passive"))
      (node (ref "Q3") (pin "2") (pinfunction "S_2") (pintype "passive"))
      (node (ref "Q3") (pin "3") (pinfunction "S_3") (pintype "passive"))
      (node (ref "Q4") (pin "5") (pinfunction "D_5") (pintype "passive"))
      (node (ref "Q4") (pin "6") (pinfunction "D_6") (pintype "passive"))
      (node (ref "Q4") (pin "7") (pinfunction "D_7") (pintype "passive"))
      (node (ref "Q4") (pin "8") (pinfunction "D_8") (pintype "passive"))
      (node (ref "Q4") (pin "TH") (pinfunction "D_TH") (pintype "passive"))
      (node (ref "R19") (pin "3") (pinfunction "1_3") (pintype "passive"))
      (node (ref "R3") (pin "2") (pinfunction "2_2") (pintype "passive"))
    )
    (net (code "92") (name "RXD_CAN") (class "Default")
      (node (ref "ATA6563") (pin "4") (pinfunction "RXD_4") (pintype "input"))
      (node (ref "LEFT") (pin "14") (pinfunction "14_14") (pintype "passive"))
    )
    (net (code "93") (name "SHUNT_HIGH_1") (class "Default")
      (node (ref "Q6") (pin "1") (pinfunction "S_1") (pintype "passive"))
      (node (ref "Q6") (pin "2") (pinfunction "S_2") (pintype "passive"))
      (node (ref "Q6") (pin "3") (pinfunction "S_3") (pintype "passive"))
      (node (ref "R75") (pin "2") (pinfunction "2_2") (pintype "passive"))
      (node (ref "R76") (pin "2") (pinfunction "2_2") (pintype "passive"))
      (node (ref "RN4") (pin "1") (pinfunction "1_1") (pintype "passive"))
    )
    (net (code "94") (name "SHUNT_HIGH_2") (class "Default")
      (node (ref "Q4") (pin "1") (pinfunction "S_1") (pintype "passive"))
      (node (ref "Q4") (pin "2") (pinfunction "S_2") (pintype "passive"))
      (node (ref "Q4") (pin "3") (pinfunction "S_3") (pintype "passive"))
      (node (ref "R53") (pin "2") (pinfunction "2_2") (pintype "passive"))
      (node (ref "R56") (pin "2") (pinfunction "2_2") (pintype "passive"))
      (node (ref "RN3") (pin "1") (pinfunction "1_1") (pintype "passive"))
    )
    (net (code "95") (name "SHUNT_HIGH_SUM") (class "Default")
      (node (ref "Q2") (pin "1") (pinfunction "S_1") (pintype "passive"))
      (node (ref "Q2") (pin "2") (pinfunction "S_2") (pintype "passive"))
      (node (ref "Q2") (pin "3") (pinfunction "S_3") (pintype "passive"))
      (node (ref "R53") (pin "1") (pinfunction "1_1") (pintype "passive"))
      (node (ref "R56") (pin "1") (pinfunction "1_1") (pintype "passive"))
      (node (ref "R7") (pin "2") (pinfunction "2_2") (pintype "passive"))
      (node (ref "R75") (pin "1") (pinfunction "1_1") (pintype "passive"))
      (node (ref "R76") (pin "1") (pinfunction "1_1") (pintype "passive"))
      (node (ref "R8") (pin "1") (pinfunction "1_1") (pintype "passive"))
      (node (ref "R9") (pin "2") (pinfunction "2_2") (pintype "passive"))
      (node (ref "RN1") (pin "1") (pinfunction "1_1") (pintype "passive"))
      (node (ref "RN3") (pin "2") (pinfunction "1_2") (pintype "passive"))
      (node (ref "RN4") (pin "2") (pinfunction "1_2") (pintype "passive"))
    )
    (net (code "96") (name "TXD_CAN") (class "Default")
      (node (ref "ATA6563") (pin "1") (pinfunction "TXD_1") (pintype "output"))
      (node (ref "RIGHT") (pin "11") (pinfunction "11_11") (pintype "passive"))
    )
    (net (code "97") (name "VDD") (class "Default")
      (node (ref "ATA6563") (pin "5") (pinfunction "VIO_5") (pintype "power_in"))
      (node (ref "C19") (pin "1") (pinfunction "1_1") (pintype "passive"))
      (node (ref "C28") (pin "1") (pinfunction "1_1") (pintype "passive"))
      (node (ref "MCP6024") (pin "4") (pinfunction "V+_4") (pintype "power_in"))
      (node (ref "R12") (pin "2") (pinfunction "2_2") (pintype "passive"))
      (node (ref "R47") (pin "2") (pinfunction "2_2") (pintype "passive"))
      (node (ref "R70") (pin "2") (pinfunction "2_2") (pintype "passive"))
      (node (ref "RIGHT") (pin "1") (pinfunction "1_1") (pintype "passive"))
      (node (ref "T1") (pin "3") (pinfunction "D_3") (pintype "passive"))
      (node (ref "T2") (pin "3") (pinfunction "D_3") (pintype "passive"))
      (node (ref "T3") (pin "3") (pinfunction "D_3") (pintype "passive"))
    )
    (net (code "98") (name "VREF") (class "Default")
      (node (ref "MCP6024") (pin "8") (pinfunction "OUT_8") (pintype "output"))
      (node (ref "MCP6024") (pin "9") (pinfunction "-IN_9") (pintype "input"))
      (node (ref "R49") (pin "1") (pinfunction "1_1") (pintype "passive"))
      (node (ref "R51") (pin "1") (pinfunction "1_1") (pintype "passive"))
      (node (ref "R52") (pin "1") (pinfunction "1_1") (pintype "passive"))
    )
    (net (code "99") (name "unconnected-(LEFT-Pad1)") (class "Default")
      (node (ref "LEFT") (pin "1") (pinfunction "1_1") (pintype "passive"))
    )
    (net (code "100") (name "unconnected-(LEFT-Pad3)") (class "Default")
      (node (ref "LEFT") (pin "3") (pinfunction "3_3") (pintype "passive"))
    )
    (net (code "101") (name "unconnected-(LEFT-Pad5)") (class "Default")
      (node (ref "LEFT") (pin "5") (pinfunction "5_5") (pintype "passive"))
    )
    (net (code "102") (name "unconnected-(LEFT-Pad8)") (class "Default")
      (node (ref "LEFT") (pin "8") (pinfunction "8_8") (pintype "passive"))
    )
    (net (code "103") (name "unconnected-(LEFT-Pad11)") (class "Default")
      (node (ref "LEFT") (pin "11") (pinfunction "11_11") (pintype "passive"))
    )
    (net (code "104") (name "unconnected-(LEFT-Pad12)") (class "Default")
      (node (ref "LEFT") (pin "12") (pinfunction "12_12") (pintype "passive"))
    )
    (net (code "105") (name "unconnected-(LEFT-Pad13)") (class "Default")
      (node (ref "LEFT") (pin "13") (pinfunction "13_13") (pintype "passive"))
    )
    (net (code "106") (name "unconnected-(MIC4607-DLY-Pad22)") (class "Default")
      (node (ref "MIC4607") (pin "22") (pinfunction "DLY_22") (pintype "input"))
    )
    (net (code "107") (name "unconnected-(MIC4607-NC-Pad1)") (class "Default")
      (node (ref "MIC4607") (pin "1") (pinfunction "NC_1") (pintype "no_connect"))
    )
    (net (code "108") (name "unconnected-(MIC4607-NC2-Pad28)") (class "Default")
      (node (ref "MIC4607") (pin "28") (pinfunction "NC2_28") (pintype "no_connect"))
    )
    (net (code "109") (name "unconnected-(RIGHT-Pad9)") (class "Default")
      (node (ref "RIGHT") (pin "9") (pinfunction "9_9") (pintype "passive"))
    )
    (net (code "110") (name "unconnected-(RIGHT-Pad10)") (class "Default")
      (node (ref "RIGHT") (pin "10") (pinfunction "10_10") (pintype "passive"))
    )
  )
)
